# TEMPERATURE_SENSOR.net
KiCad netlist of a schematic drawn in Altium Designer
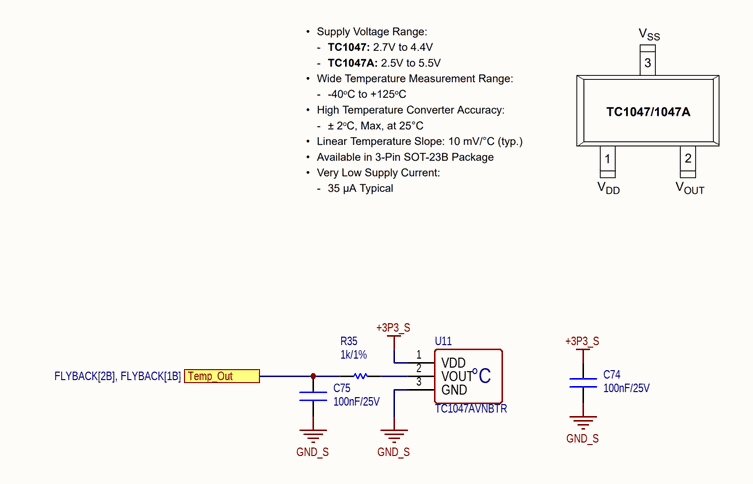
[diagram p0: TEMPERATURE_SENSOR.SchDoc]

(export (version "E")
  (design (tool "Eeschema 10.0.6"))
  (components
    (comp (ref "C74")
      (value "100nF/25V")
      (footprint "CN-SMD-0603")
      (description "CL10B104KA8NNNC")
      (libsource (lib "Library") (part "CN"))
    )
    (comp (ref "C75")
      (value "100nF/25V")
      (footprint "CN-SMD-0603")
      (description "CL10B104KA8NNNC")
      (libsource (lib "Library") (part "CN"))
    )
    (comp (ref "R35")
      (value "1k/1%")
      (footprint "RES-SMD-0603")
      (description "ERJ-3EKF1001V")
      (fields
        (field (name "MANUFACTURER") "Generic Components")
        (field (name "PUBLISHER") "Altium Hobart Technology Centre")
      )
      (libsource (lib "Library") (part "Res-SMD"))
    )
    (comp (ref "U11")
      (value "TC1047AVNBTR")
      (footprint "SOT23-132")
      (description "Precision Temperature-to-Voltage Converter")
      (libsource (lib "Library") (part "TC1047AVNBTR"))
    )
  )
  (nets
    (net (code "1") (name "+3P3_S") (class "Default")
      (node (ref "C74") (pin "2") (pinfunction "2_2") (pintype "passive"))
      (node (ref "U11") (pin "1") (pinfunction "VDD_1") (pintype "passive"))
    )
    (net (code "2") (name "/Temp_Out") (class "Default")
      (node (ref "C75") (pin "2") (pinfunction "2_2") (pintype "passive"))
      (node (ref "R35") (pin "1") (pinfunction "1_1") (pintype "passive"))
    )
    (net (code "3") (name "GND_S") (class "Default")
      (node (ref "C74") (pin "1") (pinfunction "1_1") (pintype "passive"))
      (node (ref "C75") (pin "1") (pinfunction "1_1") (pintype "passive"))
      (node (ref "U11") (pin "3") (pinfunction "GND_3") (pintype "passive"))
    )
    (net (code "4") (name "Net-(U11-VOUT)") (class "Default")
      (node (ref "R35") (pin "2") (pinfunction "2_2") (pintype "passive"))
      (node (ref "U11") (pin "2") (pinfunction "VOUT_2") (pintype "passive"))
    )
  )
)
